# hassin.net
KiCad netlist of a schematic drawn in EAGLE
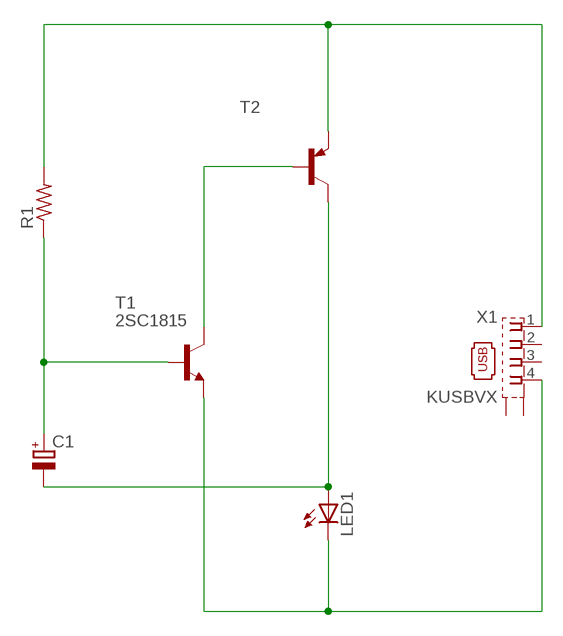
[diagram p0: schematic, sheet 1]

(export (version "E")
  (design (tool "Eeschema 10.0.6"))
  (components
    (comp (ref "C1")
      (value "CPOL-EUE2-5")
      (footprint "eagle-import:E2-5")
      (libsource (lib "eagle-import") (part "CPOL-EUE2-5"))
    )
    (comp (ref "LED1")
      (value "LED5MM")
      (footprint "eagle-import:LED5MM")
      (libsource (lib "eagle-import") (part "LED5MM"))
    )
    (comp (ref "R1")
      (value "R-US_0207/7")
      (footprint "eagle-import:0207_7")
      (libsource (lib "eagle-import") (part "R-US_0207/7"))
    )
    (comp (ref "T1")
      (value "2SC1815")
      (footprint "eagle-import:TO92-ECB")
      (libsource (lib "eagle-import") (part "2SC1815"))
    )
    (comp (ref "T2")
      (value "2SC1815-PNP-TO92-BCE")
      (footprint "eagle-import:TO92-BCE")
      (libsource (lib "eagle-import") (part "-PNP-TO92-BCE2SC1815"))
    )
    (comp (ref "X1")
      (value "KUSBVX")
      (footprint "eagle-import:KUSBVX")
      (libsource (lib "eagle-import") (part "KUSBVX"))
    )
  )
  (nets
    (net (code "1") (name "Net-(C1-Pad+)") (class "Default")
      (node (ref "C1") (pin "+") (pinfunction "+_+") (pintype "passive"))
      (node (ref "R1") (pin "1") (pinfunction "1_1") (pintype "passive"))
      (node (ref "T1") (pin "B") (pinfunction "B_B") (pintype "passive"))
    )
    (net (code "2") (name "Net-(C1-Pad-)") (class "Default")
      (node (ref "C1") (pin "-") (pinfunction "-_-") (pintype "passive"))
      (node (ref "LED1") (pin "A") (pinfunction "A_A") (pintype "passive"))
      (node (ref "T2") (pin "C") (pinfunction "C_C") (pintype "passive"))
    )
    (net (code "3") (name "Net-(LED1-C)") (class "Default")
      (node (ref "LED1") (pin "K") (pinfunction "C_K") (pintype "passive"))
      (node (ref "T1") (pin "E") (pinfunction "E_E") (pintype "passive"))
      (node (ref "X1") (pin "4") (pinfunction "4_4") (pintype "passive"))
    )
    (net (code "4") (name "Net-(R1-Pad2)") (class "Default")
      (node (ref "R1") (pin "2") (pinfunction "2_2") (pintype "passive"))
      (node (ref "T2") (pin "E") (pinfunction "E_E") (pintype "passive"))
      (node (ref "X1") (pin "1") (pinfunction "1_1") (pintype "passive"))
    )
    (net (code "5") (name "Net-(T1-PadC)") (class "Default")
      (node (ref "T1") (pin "C") (pinfunction "C_C") (pintype "passive"))
      (node (ref "T2") (pin "B") (pinfunction "B_B") (pintype "passive"))
    )
    (net (code "6") (name "unconnected-(X1-Pad2)") (class "Default")
      (node (ref "X1") (pin "2") (pinfunction "2_2") (pintype "passive"))
    )
    (net (code "7") (name "unconnected-(X1-Pad3)") (class "Default")
      (node (ref "X1") (pin "3") (pinfunction "3_3") (pintype "passive"))
    )
    (net (code "8") (name "unconnected-(X1-S1-PadM1)") (class "Default")
      (node (ref "X1") (pin "M1") (pinfunction "S1_M1") (pintype "passive"))
    )
    (net (code "9") (name "unconnected-(X1-S2-PadM2)") (class "Default")
      (node (ref "X1") (pin "M2") (pinfunction "S2_M2") (pintype "passive"))
    )
  )
)
